# LEO_COTS_no_mult_rev0.net
KiCad netlist of a schematic drawn in Altium Designer
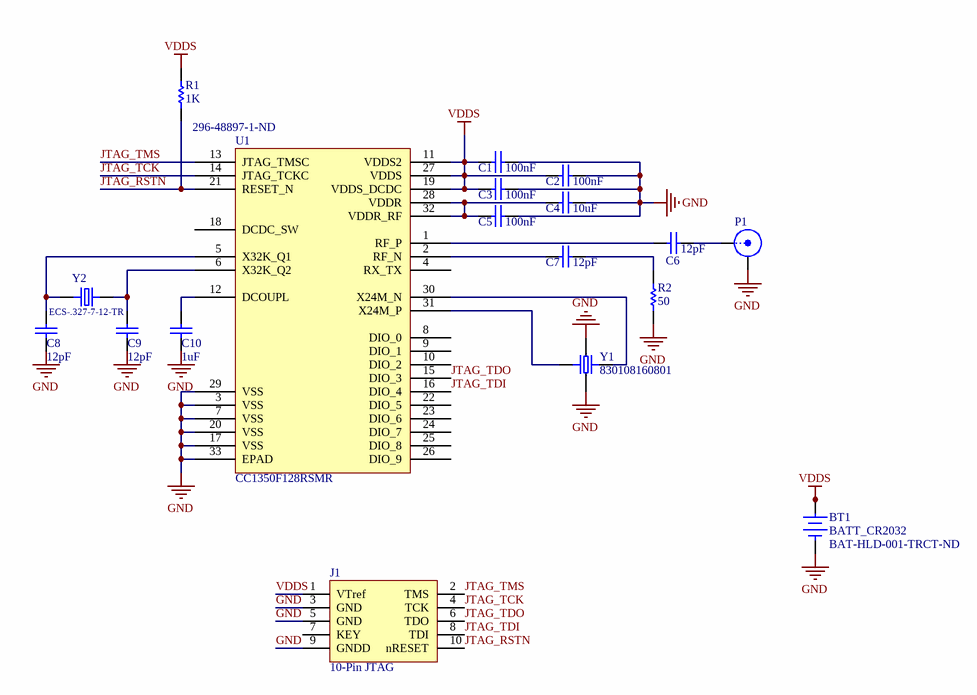
[diagram p0: LEO_COTS_no_mult_rev0.SchDoc]

(export (version "E")
  (design (tool "Eeschema 10.0.6"))
  (components
    (comp (ref "BT1")
      (value "BATT_CR2032")
      (footprint "BAT-HLD-001-TR")
      (description "CR2032 Battery Holder")
      (fields (field (name "SUPPLIER PART NUMBER 1") "BAT-HLD-001-TRCT-ND"))
      (libsource (lib "LEO_COTS_components") (part "BATT_CR2032"))
    )
    (comp (ref "C1")
      (value "100nF")
      (footprint "CAPC0603X04N")
      (description "CAP CER 100nF 0201")
      (fields (field (name "Comment") "CAP_0201"))
      (libsource (lib "LEO_COTS_components") (part "CAP_0201"))
    )
    (comp (ref "C2")
      (value "100nF")
      (footprint "CAPC0603X04N")
      (description "CAP CER 100nF 0201")
      (fields (field (name "Comment") "CAP_0201"))
      (libsource (lib "LEO_COTS_components") (part "CAP_0201"))
    )
    (comp (ref "C3")
      (value "100nF")
      (footprint "CAPC0603X04N")
      (description "CAP CER 100nF 0201")
      (fields (field (name "Comment") "CAP_0201"))
      (libsource (lib "LEO_COTS_components") (part "CAP_0201"))
    )
    (comp (ref "C4")
      (value "10uF")
      (footprint "CAPC1608X05N")
      (description "CAP CER 10uF 0603")
      (fields (field (name "Comment") "CAP_0603"))
      (libsource (lib "LEO_COTS_components") (part "CAP_0603"))
    )
    (comp (ref "C5")
      (value "100nF")
      (footprint "CAPC0603X04N")
      (description "CAP CER 100nF 0201")
      (fields (field (name "Comment") "CAP_0201"))
      (libsource (lib "LEO_COTS_components") (part "CAP_0201"))
    )
    (comp (ref "C6")
      (value "12pF")
      (footprint "1608[0603]")
      (description "CAP CER 12pF 0603")
      (fields (field (name "Comment") "CAP"))
      (libsource (lib "LEO_COTS_components") (part "CAP"))
    )
    (comp (ref "C7")
      (value "12pF")
      (footprint "CAPC0603X04N")
      (description "CAP CER 12pF 0201")
      (fields (field (name "Comment") "CAP_0201"))
      (libsource (lib "LEO_COTS_components") (part "CAP_0201"))
    )
    (comp (ref "C8")
      (value "12pF")
      (footprint "CAPC0603X04N")
      (description "CAP CER 12pF 0201")
      (fields (field (name "Comment") "CAP_0201"))
      (libsource (lib "LEO_COTS_components") (part "CAP_0201"))
    )
    (comp (ref "C9")
      (value "12pF")
      (footprint "CAPC0603X04N")
      (description "CAP CER 12pF 0201")
      (fields (field (name "Comment") "CAP_0201"))
      (libsource (lib "LEO_COTS_components") (part "CAP_0201"))
    )
    (comp (ref "C10")
      (value "1uF")
      (footprint "CAPC0603X04N")
      (description "CAP CER 1uF 0201")
      (fields (field (name "Comment") "CAP_0201"))
      (libsource (lib "LEO_COTS_components") (part "CAP_0201"))
    )
    (comp (ref "J1")
      (value "10-Pin JTAG")
      (footprint "FTSH-105-01-F-DV-007-K")
      (description "10-pin JTAG")
      (libsource (lib "LEO_COTS_components") (part "CM10"))
    )
    (comp (ref "P1")
      (value "1909763-1")
      (footprint "1909763-1")
      (description "CONN UMCC JACK STR 50OHM SMD")
      (libsource (lib "LEO_COTS_components") (part "1909763-1"))
    )
    (comp (ref "R1")
      (value "1K")
      (footprint "CAPC0603X04N")
      (description "RES 1K OHM 0201")
      (fields (field (name "Comment") "RES_0201") (field (name "PUBLISHER") "Altium Limited"))
      (libsource (lib "LEO_COTS_components") (part "Res Semi"))
    )
    (comp (ref "R2")
      (value "50")
      (footprint "CAPC0603X04N")
      (description "RES 50 OHM 0201")
      (fields (field (name "Comment") "RES_0201") (field (name "PUBLISHER") "Altium Limited"))
      (libsource (lib "LEO_COTS_components") (part "Res Semi"))
    )
    (comp (ref "U1")
      (value "CC1350F128RSMR")
      (footprint "QFN40P400X400X100-33N")
      (description "Ultra-Low-Power Dual-Band Wireless MCU")
      (fields (field (name "SUPPLIER PART NUMBER 1") "296-48897-1-ND"))
      (libsource (lib "LEO_COTS_components") (part "CC1350F128RSMR"))
    )
    (comp (ref "Y1")
      (value "830108160801")
      (footprint "LFXTAL081608")
      (description "24 MHz crystal")
      (fields (field (name "MP") "ECS-.327-7-12-TR"))
      (libsource (lib "LEO_COTS_components") (part "830108160801"))
    )
    (comp (ref "Y2")
      (value "ECS-.327-7-12-TR")
      (footprint "XTAL_ECS-.327-7-12-TR")
      (description "32.768 kHz SMD Crystal")
      (libsource (lib "LEO_COTS_components") (part "ECS-.327-7-12-TR"))
    )
  )
  (nets
    (net (code "1") (name "/JTAG_RSTN") (class "Default")
      (node (ref "J1") (pin "10") (pinfunction "nRESET_10") (pintype "passive"))
      (node (ref "R1") (pin "1") (pinfunction "1_1") (pintype "passive"))
      (node (ref "U1") (pin "21") (pinfunction "RESET_N_21") (pintype "passive"))
    )
    (net (code "2") (name "/JTAG_TCK") (class "Default")
      (node (ref "J1") (pin "4") (pinfunction "TCK_4") (pintype "passive"))
      (node (ref "U1") (pin "14") (pinfunction "JTAG_TCKC_14") (pintype "passive"))
    )
    (net (code "3") (name "/JTAG_TDI") (class "Default")
      (node (ref "J1") (pin "8") (pinfunction "TDI_8") (pintype "passive"))
      (node (ref "U1") (pin "16") (pinfunction "DIO_4_16") (pintype "passive"))
    )
    (net (code "4") (name "/JTAG_TDO") (class "Default")
      (node (ref "J1") (pin "6") (pinfunction "TDO_6") (pintype "passive"))
      (node (ref "U1") (pin "15") (pinfunction "DIO_3_15") (pintype "passive"))
    )
    (net (code "5") (name "/JTAG_TMS") (class "Default")
      (node (ref "J1") (pin "2") (pinfunction "TMS_2") (pintype "passive"))
      (node (ref "U1") (pin "13") (pinfunction "JTAG_TMSC_13") (pintype "passive"))
    )
    (net (code "6") (name "GND") (class "Default")
      (node (ref "BT1") (pin "N1") (pinfunction "-_N1") (pintype "passive"))
      (node (ref "C1") (pin "1") (pinfunction "1_1") (pintype "passive"))
      (node (ref "C10") (pin "1") (pinfunction "1_1") (pintype "passive"))
      (node (ref "C2") (pin "1") (pinfunction "1_1") (pintype "passive"))
      (node (ref "C3") (pin "1") (pinfunction "1_1") (pintype "passive"))
      (node (ref "C4") (pin "2") (pinfunction "2_2") (pintype "passive"))
      (node (ref "C5") (pin "1") (pinfunction "1_1") (pintype "passive"))
      (node (ref "C8") (pin "1") (pinfunction "1_1") (pintype "passive"))
      (node (ref "C9") (pin "1") (pinfunction "1_1") (pintype "passive"))
      (node (ref "J1") (pin "3") (pinfunction "GND_3") (pintype "passive"))
      (node (ref "J1") (pin "5") (pinfunction "GND_5") (pintype "passive"))
      (node (ref "J1") (pin "9") (pinfunction "GNDD_9") (pintype "passive"))
      (node (ref "P1") (pin "2") (pinfunction "Y_2") (pintype "passive"))
      (node (ref "R2") (pin "1") (pinfunction "1_1") (pintype "passive"))
      (node (ref "U1") (pin "17") (pinfunction "VSS_17") (pintype "passive"))
      (node (ref "U1") (pin "20") (pinfunction "VSS_20") (pintype "passive"))
      (node (ref "U1") (pin "29") (pinfunction "VSS_29") (pintype "passive"))
      (node (ref "U1") (pin "3") (pinfunction "VSS_3") (pintype "passive"))
      (node (ref "U1") (pin "33") (pinfunction "EPAD_33") (pintype "passive"))
      (node (ref "U1") (pin "7") (pinfunction "VSS_7") (pintype "passive"))
      (node (ref "Y1") (pin "2") (pinfunction "2_2") (pintype "passive"))
      (node (ref "Y1") (pin "4") (pinfunction "4_4") (pintype "passive"))
    )
    (net (code "7") (name "Net-(C7-Pad1)") (class "Default")
      (node (ref "C7") (pin "1") (pinfunction "1_1") (pintype "passive"))
      (node (ref "R2") (pin "2") (pinfunction "2_2") (pintype "passive"))
    )
    (net (code "8") (name "Net-(P1-X)") (class "Default")
      (node (ref "C6") (pin "2") (pinfunction "2_2") (pintype "passive"))
      (node (ref "P1") (pin "1") (pinfunction "X_1") (pintype "passive"))
    )
    (net (code "9") (name "Net-(U1-DCOUPL)") (class "Default")
      (node (ref "C10") (pin "2") (pinfunction "2_2") (pintype "passive"))
      (node (ref "U1") (pin "12") (pinfunction "DCOUPL_12") (pintype "passive"))
    )
    (net (code "10") (name "Net-(U1-RF_N)") (class "Default")
      (node (ref "C7") (pin "2") (pinfunction "2_2") (pintype "passive"))
      (node (ref "U1") (pin "2") (pinfunction "RF_N_2") (pintype "passive"))
    )
    (net (code "11") (name "Net-(U1-RF_P)") (class "Default")
      (node (ref "C6") (pin "1") (pinfunction "1_1") (pintype "passive"))
      (node (ref "U1") (pin "1") (pinfunction "RF_P_1") (pintype "passive"))
    )
    (net (code "12") (name "Net-(U1-VDDR)") (class "Default")
      (node (ref "C4") (pin "1") (pinfunction "1_1") (pintype "passive"))
      (node (ref "C5") (pin "2") (pinfunction "2_2") (pintype "passive"))
      (node (ref "U1") (pin "28") (pinfunction "VDDR_28") (pintype "passive"))
      (node (ref "U1") (pin "32") (pinfunction "VDDR_RF_32") (pintype "passive"))
    )
    (net (code "13") (name "Net-(U1-X24M_N)") (class "Default")
      (node (ref "U1") (pin "30") (pinfunction "X24M_N_30") (pintype "passive"))
      (node (ref "Y1") (pin "3") (pinfunction "3_3") (pintype "passive"))
    )
    (net (code "14") (name "Net-(U1-X24M_P)") (class "Default")
      (node (ref "U1") (pin "31") (pinfunction "X24M_P_31") (pintype "passive"))
      (node (ref "Y1") (pin "1") (pinfunction "1_1") (pintype "passive"))
    )
    (net (code "15") (name "Net-(U1-X32K_Q1)") (class "Default")
      (node (ref "C8") (pin "2") (pinfunction "2_2") (pintype "passive"))
      (node (ref "U1") (pin "5") (pinfunction "X32K_Q1_5") (pintype "passive"))
      (node (ref "Y2") (pin "1") (pinfunction "1_1") (pintype "passive"))
    )
    (net (code "16") (name "Net-(U1-X32K_Q2)") (class "Default")
      (node (ref "C9") (pin "2") (pinfunction "2_2") (pintype "passive"))
      (node (ref "U1") (pin "6") (pinfunction "X32K_Q2_6") (pintype "passive"))
      (node (ref "Y2") (pin "2") (pinfunction "2_2") (pintype "passive"))
    )
    (net (code "17") (name "VDDS") (class "Default")
      (node (ref "BT1") (pin "P1") (pinfunction "+_P1") (pintype "passive"))
      (node (ref "BT1") (pin "P2") (pinfunction "+_P2") (pintype "passive"))
      (node (ref "C1") (pin "2") (pinfunction "2_2") (pintype "passive"))
      (node (ref "C2") (pin "2") (pinfunction "2_2") (pintype "passive"))
      (node (ref "C3") (pin "2") (pinfunction "2_2") (pintype "passive"))
      (node (ref "J1") (pin "1") (pinfunction "VTref_1") (pintype "passive"))
      (node (ref "R1") (pin "2") (pinfunction "2_2") (pintype "passive"))
      (node (ref "U1") (pin "11") (pinfunction "VDDS2_11") (pintype "passive"))
      (node (ref "U1") (pin "19") (pinfunction "VDDS_DCDC_19") (pintype "passive"))
      (node (ref "U1") (pin "27") (pinfunction "VDDS_27") (pintype "passive"))
    )
    (net (code "18") (name "unconnected-(J1-KEY-Pad7)") (class "Default")
      (node (ref "J1") (pin "7") (pinfunction "KEY_7") (pintype "passive"))
    )
    (net (code "19") (name "unconnected-(U1-DCDC_SW-Pad18)") (class "Default")
      (node (ref "U1") (pin "18") (pinfunction "DCDC_SW_18") (pintype "passive"))
    )
    (net (code "20") (name "unconnected-(U1-DIO_0-Pad8)") (class "Default")
      (node (ref "U1") (pin "8") (pinfunction "DIO_0_8") (pintype "passive"))
    )
    (net (code "21") (name "unconnected-(U1-DIO_1-Pad9)") (class "Default")
      (node (ref "U1") (pin "9") (pinfunction "DIO_1_9") (pintype "passive"))
    )
    (net (code "22") (name "unconnected-(U1-DIO_2-Pad10)") (class "Default")
      (node (ref "U1") (pin "10") (pinfunction "DIO_2_10") (pintype "passive"))
    )
    (net (code "23") (name "unconnected-(U1-DIO_5-Pad22)") (class "Default")
      (node (ref "U1") (pin "22") (pinfunction "DIO_5_22") (pintype "passive"))
    )
    (net (code "24") (name "unconnected-(U1-DIO_6-Pad23)") (class "Default")
      (node (ref "U1") (pin "23") (pinfunction "DIO_6_23") (pintype "passive"))
    )
    (net (code "25") (name "unconnected-(U1-DIO_7-Pad24)") (class "Default")
      (node (ref "U1") (pin "24") (pinfunction "DIO_7_24") (pintype "passive"))
    )
    (net (code "26") (name "unconnected-(U1-DIO_8-Pad25)") (class "Default")
      (node (ref "U1") (pin "25") (pinfunction "DIO_8_25") (pintype "passive"))
    )
    (net (code "27") (name "unconnected-(U1-DIO_9-Pad26)") (class "Default")
      (node (ref "U1") (pin "26") (pinfunction "DIO_9_26") (pintype "passive"))
    )
    (net (code "28") (name "unconnected-(U1-RX_TX-Pad4)") (class "Default")
      (node (ref "U1") (pin "4") (pinfunction "RX_TX_4") (pintype "passive"))
    )
  )
)
